# SPEC_A7_Power.net
KiCad netlist of a schematic drawn in Altium Designer
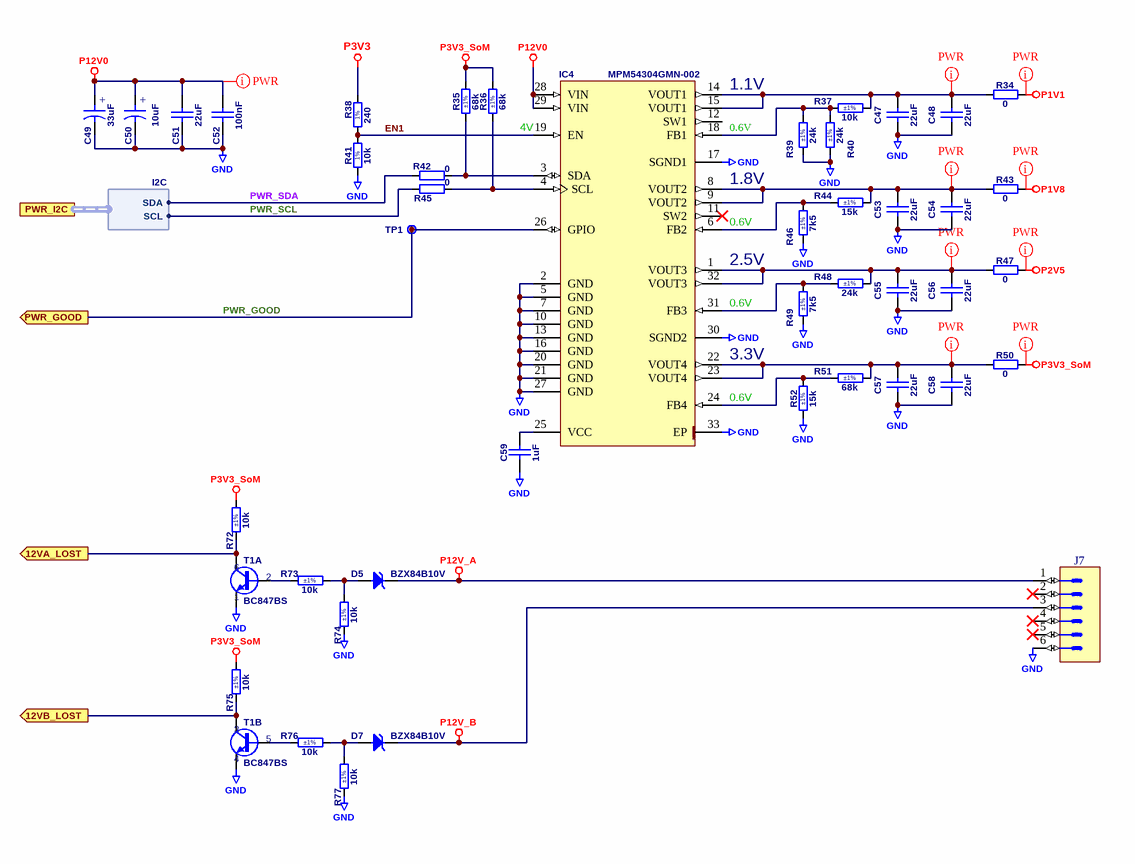
[diagram p0: SPEC_A7_Power.SchDoc]

(export (version "E")
  (design (tool "Eeschema 10.0.6"))
  (components
    (comp (ref "C47")
      (value "22uF")
      (footprint "CAPC2012X135N")
      (description "Non-polarised capacitor")
      (fields
        (field (name "MANUFACTURER PART NUMBER") "CC0805_22UF_16V_10%_X5R")
        (field (name "MANUFACTURER") "GENERIC")
        (field (name "AUTHOR") "CERN DEM JLC")
      )
      (libsource (lib "Capacitors") (part "Capacitor - non polarized"))
    )
    (comp (ref "C48")
      (value "22uF")
      (footprint "CAPC2012X135N")
      (description "Non-polarised capacitor")
      (fields
        (field (name "MANUFACTURER PART NUMBER") "CC0805_22UF_16V_10%_X5R")
        (field (name "MANUFACTURER") "GENERIC")
        (field (name "AUTHOR") "CERN DEM JLC")
      )
      (libsource (lib "Capacitors") (part "Capacitor - non polarized"))
    )
    (comp (ref "C49")
      (value "33uF")
      (footprint "CAPMP3528X210N")
      (description "Polarised capacitor")
      (fields
        (field (name "PART NUMBER") "CTE3528-21_33UF_16V_10%")
        (field (name "VOLTAGE") "16V")
        (field (name "AUTHOR") "CERN DEM JLC")
      )
      (libsource (lib "Capacitors") (part "Capacitor - polarized"))
    )
    (comp (ref "C50")
      (value "10uF")
      (footprint "CAPMP3216X180N")
      (description "Polarised capacitor")
      (fields
        (field (name "PART NUMBER") "CTE3216-18_10UF_16V_20%_AVX_TCJ")
        (field (name "VOLTAGE") "16V")
        (field (name "AUTHOR") "CERN DEM JLC")
      )
      (libsource (lib "Capacitors") (part "Capacitor - polarized"))
    )
    (comp (ref "C51")
      (value "22uF")
      (footprint "CAPC2012X135N")
      (description "Non-polarised capacitor")
      (fields
        (field (name "MANUFACTURER PART NUMBER") "CC0805_22UF_16V_10%_X5R")
        (field (name "MANUFACTURER") "GENERIC")
        (field (name "AUTHOR") "CERN DEM JLC")
      )
      (libsource (lib "Capacitors") (part "Capacitor - non polarized"))
    )
    (comp (ref "C52")
      (value "100nF")
      (footprint "CAPC1005X55N")
      (description "Non-polarised capacitor")
      (fields
        (field (name "PART NUMBER") "CC0402_100NF_16V_10%_X7R")
        (field (name "VOLTAGE") "16V")
        (field (name "AUTHOR") "CERN DEM JLC")
      )
      (libsource (lib "Capacitors") (part "Capacitor - non polarized"))
    )
    (comp (ref "C53")
      (value "22uF")
      (footprint "CAPC2012X135N")
      (description "Non-polarised capacitor")
      (fields
        (field (name "MANUFACTURER PART NUMBER") "CC0805_22UF_16V_10%_X5R")
        (field (name "MANUFACTURER") "GENERIC")
        (field (name "AUTHOR") "CERN DEM JLC")
      )
      (libsource (lib "Capacitors") (part "Capacitor - non polarized"))
    )
    (comp (ref "C54")
      (value "22uF")
      (footprint "CAPC2012X135N")
      (description "Non-polarised capacitor")
      (fields
        (field (name "MANUFACTURER PART NUMBER") "CC0805_22UF_16V_10%_X5R")
        (field (name "MANUFACTURER") "GENERIC")
        (field (name "AUTHOR") "CERN DEM JLC")
      )
      (libsource (lib "Capacitors") (part "Capacitor - non polarized"))
    )
    (comp (ref "C55")
      (value "22uF")
      (footprint "CAPC2012X135N")
      (description "Non-polarised capacitor")
      (fields
        (field (name "MANUFACTURER PART NUMBER") "CC0805_22UF_16V_10%_X5R")
        (field (name "MANUFACTURER") "GENERIC")
        (field (name "AUTHOR") "CERN DEM JLC")
      )
      (libsource (lib "Capacitors") (part "Capacitor - non polarized"))
    )
    (comp (ref "C56")
      (value "22uF")
      (footprint "CAPC2012X135N")
      (description "Non-polarised capacitor")
      (fields
        (field (name "MANUFACTURER PART NUMBER") "CC0805_22UF_16V_10%_X5R")
        (field (name "MANUFACTURER") "GENERIC")
        (field (name "AUTHOR") "CERN DEM JLC")
      )
      (libsource (lib "Capacitors") (part "Capacitor - non polarized"))
    )
    (comp (ref "C57")
      (value "22uF")
      (footprint "CAPC2012X135N")
      (description "Non-polarised capacitor")
      (fields
        (field (name "MANUFACTURER PART NUMBER") "CC0805_22UF_16V_10%_X5R")
        (field (name "MANUFACTURER") "GENERIC")
        (field (name "AUTHOR") "CERN DEM JLC")
      )
      (libsource (lib "Capacitors") (part "Capacitor - non polarized"))
    )
    (comp (ref "C58")
      (value "22uF")
      (footprint "CAPC2012X135N")
      (description "Non-polarised capacitor")
      (fields
        (field (name "MANUFACTURER PART NUMBER") "CC0805_22UF_16V_10%_X5R")
        (field (name "MANUFACTURER") "GENERIC")
        (field (name "AUTHOR") "CERN DEM JLC")
      )
      (libsource (lib "Capacitors") (part "Capacitor - non polarized"))
    )
    (comp (ref "C59")
      (value "1uF")
      (footprint "CAPC1005X55N")
      (description "Non-polarised capacitor")
      (fields
        (field (name "PART NUMBER") "CC0402_1UF_16V_10%_X5R")
        (field (name "VOLTAGE") "16V")
        (field (name "AUTHOR") "CERN DEM JLC")
      )
      (libsource (lib "Capacitors") (part "Capacitor - non polarized"))
    )
    (comp (ref "D5")
      (value "BZX84B10V")
      (footprint "SOT95P248X115-3N")
      (description "Diode Zener Anode Pin 1 Cathode Pin 3 (Pas de pin 2)")
      (fields
        (field (name "VOLTAGE") "10V")
        (field (name "POWER") "300mW")
        (field (name "AUTHOR") "CERN DEM JLC")
      )
      (libsource (lib "ICs And Semiconductors") (part "Diode Zener A1C3"))
    )
    (comp (ref "D7")
      (value "BZX84B10V")
      (footprint "SOT95P248X115-3N")
      (description "Diode Zener Anode Pin 1 Cathode Pin 3 (Pas de pin 2)")
      (fields
        (field (name "VOLTAGE") "10V")
        (field (name "POWER") "300mW")
        (field (name "AUTHOR") "CERN DEM JLC")
      )
      (libsource (lib "ICs And Semiconductors") (part "Diode Zener A1C3"))
    )
    (comp (ref "IC4")
      (value "MPM54304GMN-002")
      (footprint "MPS_MPM54304GMN")
      (description "Quad-Output Power Module with I2C and MTP")
      (fields
        (field (name "MANUFACTURER") "MPS (MONOLITIC  POWER SYSTEMS)")
        (field (name "AUTHOR") "CERN DEM BC")
      )
      (libsource (lib "ICs And Semiconductors") (part "MPM54304GMN"))
    )
    (comp (ref "J7")
      (value "Header 6")
      (footprint "3M_N2506-6002RB")
      (description "Connector 6 Male")
      (fields
        (field (name "PART NUMBER") "3M_N2506-6002RB")
        (field (name "MANUFACTURER") "3M")
        (field (name "AUTHOR") "CERN DEM JLC")
      )
      (libsource (lib "Connectors") (part "Connector 6 Male"))
    )
    (comp (ref "R34")
      (value "0")
      (footprint "RESC2012X60N")
      (description "Resistor")
      (fields
        (field (name "PART NUMBER") "R0805_0R_JUMPER")
        (field (name "MANUFACTURER") "GENERIC")
        (field (name "AUTHOR") "CERN DEM JLC")
      )
      (libsource (lib "Resistors") (part "Resistor"))
    )
    (comp (ref "R35")
      (value "68k")
      (footprint "RESC1005X40N")
      (description "Resistor - 1%")
      (fields
        (field (name "TOLERANCE") "±1%")
        (field (name "PART NUMBER") "R0402_68K_1%_0.0625W_100PPM")
        (field (name "POWER") "0.0625W")
        (field (name "AUTHOR") "CERN DEM JLC")
      )
      (libsource (lib "Resistors") (part "Resistor - 1%"))
    )
    (comp (ref "R36")
      (value "68k")
      (footprint "RESC1005X40N")
      (description "Resistor - 1%")
      (fields
        (field (name "TOLERANCE") "±1%")
        (field (name "PART NUMBER") "R0402_68K_1%_0.0625W_100PPM")
        (field (name "POWER") "0.0625W")
        (field (name "AUTHOR") "CERN DEM JLC")
      )
      (libsource (lib "Resistors") (part "Resistor - 1%"))
    )
    (comp (ref "R37")
      (value "10k")
      (footprint "RESC1005X40N")
      (description "Resistor - 1%")
      (fields
        (field (name "TOLERANCE") "±1%")
        (field (name "PART NUMBER") "R0402_10K_1%_0.0625W_100PPM")
        (field (name "POWER") "0.0625W")
        (field (name "AUTHOR") "CERN DEM JLC")
      )
      (libsource (lib "Resistors") (part "Resistor - 1%"))
    )
    (comp (ref "R38")
      (value "240")
      (footprint "RESC1005X40N")
      (description "Resistor - 1%")
      (fields
        (field (name "PART NUMBER") "R0402_240R_1%_0.0625W_100PPM")
        (field (name "POWER") "0.0625W")
        (field (name "AUTHOR") "CERN DEM JLC")
      )
      (libsource (lib "Resistors") (part "Resistor - 1%"))
    )
    (comp (ref "R39")
      (value "24k")
      (footprint "RESC1005X40N")
      (description "Resistor - 1%")
      (fields
        (field (name "TOLERANCE") "±1%")
        (field (name "PART NUMBER") "R0402_24K_1%_0.0625W_100PPM")
        (field (name "POWER") "0.0625W")
        (field (name "AUTHOR") "CERN DEM JLC")
      )
      (libsource (lib "Resistors") (part "Resistor - 1%"))
    )
    (comp (ref "R40")
      (value "24k")
      (footprint "RESC1005X40N")
      (description "Resistor - 1%")
      (fields
        (field (name "TOLERANCE") "±1%")
        (field (name "PART NUMBER") "R0402_24K_1%_0.0625W_100PPM")
        (field (name "POWER") "0.0625W")
        (field (name "AUTHOR") "CERN DEM JLC")
      )
      (libsource (lib "Resistors") (part "Resistor - 1%"))
    )
    (comp (ref "R41")
      (value "10k")
      (footprint "RESC1005X40N")
      (description "Resistor - 1%")
      (fields
        (field (name "PART NUMBER") "R0402_10K_1%_0.0625W_100PPM")
        (field (name "POWER") "0.0625W")
        (field (name "AUTHOR") "CERN DEM JLC")
      )
      (libsource (lib "Resistors") (part "Resistor - 1%"))
    )
    (comp (ref "R42")
      (value "0")
      (footprint "RESC1005X40N")
      (description "Resistor")
      (fields
        (field (name "PART NUMBER") "R0402_0R_JUMPER")
        (field (name "MANUFACTURER") "GENERIC")
        (field (name "AUTHOR") "CERN DEM JLC")
      )
      (libsource (lib "Resistors") (part "Resistor"))
    )
    (comp (ref "R43")
      (value "0")
      (footprint "RESC2012X60N")
      (description "Resistor")
      (fields
        (field (name "PART NUMBER") "R0805_0R_JUMPER")
        (field (name "MANUFACTURER") "GENERIC")
        (field (name "AUTHOR") "CERN DEM JLC")
      )
      (libsource (lib "Resistors") (part "Resistor"))
    )
    (comp (ref "R44")
      (value "15k")
      (footprint "RESC1005X40N")
      (description "Resistor - 1%")
      (fields
        (field (name "TOLERANCE") "±1%")
        (field (name "PART NUMBER") "R0402_15K_1%_0.0625W_100PPM")
        (field (name "POWER") "0.0625W")
        (field (name "AUTHOR") "CERN DEM JMW")
      )
      (libsource (lib "Resistors") (part "Resistor - 1%"))
    )
    (comp (ref "R45")
      (value "0")
      (footprint "RESC1005X40N")
      (description "Resistor")
      (fields
        (field (name "PART NUMBER") "R0402_0R_JUMPER")
        (field (name "MANUFACTURER") "GENERIC")
        (field (name "AUTHOR") "CERN DEM JLC")
      )
      (libsource (lib "Resistors") (part "Resistor"))
    )
    (comp (ref "R46")
      (value "7k5")
      (footprint "RESC1005X40N")
      (description "Resistor - 1%")
      (fields
        (field (name "TOLERANCE") "±1%")
        (field (name "PART NUMBER") "R0402_7K5_1%_0.0625W_100PPM")
        (field (name "POWER") "0.0625W")
        (field (name "AUTHOR") "CERN DEM JLC")
      )
      (libsource (lib "Resistors") (part "Resistor - 1%"))
    )
    (comp (ref "R47")
      (value "0")
      (footprint "RESC2012X60N")
      (description "Resistor")
      (fields
        (field (name "PART NUMBER") "R0805_0R_JUMPER")
        (field (name "MANUFACTURER") "GENERIC")
        (field (name "AUTHOR") "CERN DEM JLC")
      )
      (libsource (lib "Resistors") (part "Resistor"))
    )
    (comp (ref "R48")
      (value "24k")
      (footprint "RESC1005X40N")
      (description "Resistor - 1%")
      (fields
        (field (name "TOLERANCE") "±1%")
        (field (name "PART NUMBER") "R0402_24K_1%_0.0625W_100PPM")
        (field (name "POWER") "0.0625W")
        (field (name "AUTHOR") "CERN DEM JLC")
      )
      (libsource (lib "Resistors") (part "Resistor - 1%"))
    )
    (comp (ref "R49")
      (value "7k5")
      (footprint "RESC1005X40N")
      (description "Resistor - 1%")
      (fields
        (field (name "TOLERANCE") "±1%")
        (field (name "PART NUMBER") "R0402_7K5_1%_0.0625W_100PPM")
        (field (name "POWER") "0.0625W")
        (field (name "AUTHOR") "CERN DEM JLC")
      )
      (libsource (lib "Resistors") (part "Resistor - 1%"))
    )
    (comp (ref "R50")
      (value "0")
      (footprint "RESC2012X60N")
      (description "Resistor")
      (fields
        (field (name "PART NUMBER") "R0805_0R_JUMPER")
        (field (name "MANUFACTURER") "GENERIC")
        (field (name "AUTHOR") "CERN DEM JLC")
      )
      (libsource (lib "Resistors") (part "Resistor"))
    )
    (comp (ref "R51")
      (value "68k")
      (footprint "RESC1005X40N")
      (description "Resistor - 1%")
      (fields
        (field (name "TOLERANCE") "±1%")
        (field (name "PART NUMBER") "R0402_68K_1%_0.0625W_100PPM")
        (field (name "POWER") "0.0625W")
        (field (name "AUTHOR") "CERN DEM JLC")
      )
      (libsource (lib "Resistors") (part "Resistor - 1%"))
    )
    (comp (ref "R52")
      (value "15k")
      (footprint "RESC1005X40N")
      (description "Resistor - 1%")
      (fields
        (field (name "TOLERANCE") "±1%")
        (field (name "PART NUMBER") "R0402_15K_1%_0.0625W_100PPM")
        (field (name "POWER") "0.0625W")
        (field (name "AUTHOR") "CERN DEM JMW")
      )
      (libsource (lib "Resistors") (part "Resistor - 1%"))
    )
    (comp (ref "R72")
      (value "10k")
      (footprint "RESC1005X40N")
      (description "Resistor - 1%")
      (fields
        (field (name "TOLERANCE") "±1%")
        (field (name "PART NUMBER") "R0402_10K_1%_0.0625W_100PPM")
        (field (name "POWER") "0.0625W")
        (field (name "AUTHOR") "CERN DEM JLC")
      )
      (libsource (lib "Resistors") (part "Resistor - 1%"))
    )
    (comp (ref "R73")
      (value "10k")
      (footprint "RESC1005X40N")
      (description "Resistor - 1%")
      (fields
        (field (name "TOLERANCE") "±1%")
        (field (name "PART NUMBER") "R0402_10K_1%_0.0625W_100PPM")
        (field (name "POWER") "0.0625W")
        (field (name "AUTHOR") "CERN DEM JLC")
      )
      (libsource (lib "Resistors") (part "Resistor - 1%"))
    )
    (comp (ref "R74")
      (value "10k")
      (footprint "RESC1005X40N")
      (description "Resistor - 1%")
      (fields
        (field (name "TOLERANCE") "±1%")
        (field (name "PART NUMBER") "R0402_10K_1%_0.0625W_100PPM")
        (field (name "POWER") "0.0625W")
        (field (name "AUTHOR") "CERN DEM JLC")
      )
      (libsource (lib "Resistors") (part "Resistor - 1%"))
    )
    (comp (ref "R75")
      (value "10k")
      (footprint "RESC1005X40N")
      (description "Resistor - 1%")
      (fields
        (field (name "TOLERANCE") "±1%")
        (field (name "PART NUMBER") "R0402_10K_1%_0.0625W_100PPM")
        (field (name "POWER") "0.0625W")
        (field (name "AUTHOR") "CERN DEM JLC")
      )
      (libsource (lib "Resistors") (part "Resistor - 1%"))
    )
    (comp (ref "R76")
      (value "10k")
      (footprint "RESC1005X40N")
      (description "Resistor - 1%")
      (fields
        (field (name "TOLERANCE") "±1%")
        (field (name "PART NUMBER") "R0402_10K_1%_0.0625W_100PPM")
        (field (name "POWER") "0.0625W")
        (field (name "AUTHOR") "CERN DEM JLC")
      )
      (libsource (lib "Resistors") (part "Resistor - 1%"))
    )
    (comp (ref "R77")
      (value "10k")
      (footprint "RESC1005X40N")
      (description "Resistor - 1%")
      (fields
        (field (name "TOLERANCE") "±1%")
        (field (name "PART NUMBER") "R0402_10K_1%_0.0625W_100PPM")
        (field (name "POWER") "0.0625W")
        (field (name "AUTHOR") "CERN DEM JLC")
      )
      (libsource (lib "Resistors") (part "Resistor - 1%"))
    )
    (comp (ref "T1")
      (value "BC847BS")
      (footprint "SOT65P210X110-6N")
      (description "45V, 100mA Dual NPN General-Purpose Transistor")
      (fields (field (name "MANUFACTURER") "NXP SEMICONDUCTORS") (field (name "AUTHOR") "CERN DEM JMW"))
      (libsource (lib "ICs And Semiconductors") (part "BC847BS"))
    )
    (comp (ref "TP1")
      (value "Test Point")
      (footprint "TPS127")
      (fields (field (name "PART NUMBER") "SMD_PAD_1.27X1.27MM") (field (name "AUTHOR") "CERN DEM JLC"))
      (libsource (lib "Eletro-mechanical") (part "Test Point"))
    )
  )
  (nets
    (net (code "2") (name "/12VA_LOST") (class "Default")
      (node (ref "R72") (pin "1") (pinfunction "1_1") (pintype "passive"))
      (node (ref "T1") (pin "6") (pinfunction "C_6") (pintype "passive"))
    )
    (net (code "3") (name "/12VB_LOST") (class "Default")
      (node (ref "R75") (pin "1") (pinfunction "1_1") (pintype "passive"))
      (node (ref "T1") (pin "3") (pinfunction "C_3") (pintype "passive"))
    )
    (net (code "4") (name "/EN1") (class "Default")
      (node (ref "IC4") (pin "19") (pinfunction "EN_19") (pintype "input"))
      (node (ref "R38") (pin "1") (pinfunction "1_1") (pintype "passive"))
      (node (ref "R41") (pin "2") (pinfunction "2_2") (pintype "passive"))
    )
    (net (code "5") (name "/PWR_GOOD") (class "Default")
      (node (ref "IC4") (pin "26") (pinfunction "GPIO_26") (pintype "bidirectional"))
      (node (ref "TP1") (pin "1") (pinfunction "1_1") (pintype "bidirectional"))
    )
    (net (code "6") (name "/PWR_SCL") (class "Default")
      (node (ref "R45") (pin "1") (pinfunction "1_1") (pintype "passive"))
    )
    (net (code "7") (name "/PWR_SDA") (class "Default")
      (node (ref "R42") (pin "1") (pinfunction "1_1") (pintype "passive"))
    )
    (net (code "9") (name "GND") (class "Default")
      (node (ref "C47") (pin "1") (pinfunction "1_1") (pintype "passive"))
      (node (ref "C48") (pin "1") (pinfunction "1_1") (pintype "passive"))
      (node (ref "C49") (pin "2") (pinfunction "2_2") (pintype "passive"))
      (node (ref "C50") (pin "2") (pinfunction "2_2") (pintype "passive"))
      (node (ref "C51") (pin "1") (pinfunction "1_1") (pintype "passive"))
      (node (ref "C52") (pin "1") (pinfunction "1_1") (pintype "passive"))
      (node (ref "C53") (pin "1") (pinfunction "1_1") (pintype "passive"))
      (node (ref "C54") (pin "1") (pinfunction "1_1") (pintype "passive"))
      (node (ref "C55") (pin "1") (pinfunction "1_1") (pintype "passive"))
      (node (ref "C56") (pin "1") (pinfunction "1_1") (pintype "passive"))
      (node (ref "C57") (pin "1") (pinfunction "1_1") (pintype "passive"))
      (node (ref "C58") (pin "1") (pinfunction "1_1") (pintype "passive"))
      (node (ref "C59") (pin "1") (pinfunction "1_1") (pintype "passive"))
      (node (ref "IC4") (pin "10") (pinfunction "GND_10") (pintype "power_in"))
      (node (ref "IC4") (pin "13") (pinfunction "GND_13") (pintype "power_in"))
      (node (ref "IC4") (pin "16") (pinfunction "GND_16") (pintype "power_in"))
      (node (ref "IC4") (pin "17") (pinfunction "SGND1_17") (pintype "power_in"))
      (node (ref "IC4") (pin "2") (pinfunction "GND_2") (pintype "power_in"))
      (node (ref "IC4") (pin "20") (pinfunction "GND_20") (pintype "power_in"))
      (node (ref "IC4") (pin "21") (pinfunction "GND_21") (pintype "power_in"))
      (node (ref "IC4") (pin "27") (pinfunction "GND_27") (pintype "power_in"))
      (node (ref "IC4") (pin "30") (pinfunction "SGND2_30") (pintype "power_in"))
      (node (ref "IC4") (pin "33") (pinfunction "EP_33") (pintype "power_in"))
      (node (ref "IC4") (pin "5") (pinfunction "GND_5") (pintype "power_in"))
      (node (ref "IC4") (pin "7") (pinfunction "GND_7") (pintype "power_in"))
      (node (ref "J7") (pin "6") (pinfunction "6_6") (pintype "bidirectional"))
      (node (ref "R39") (pin "1") (pinfunction "1_1") (pintype "passive"))
      (node (ref "R40") (pin "1") (pinfunction "1_1") (pintype "passive"))
      (node (ref "R41") (pin "1") (pinfunction "1_1") (pintype "passive"))
      (node (ref "R46") (pin "1") (pinfunction "1_1") (pintype "passive"))
      (node (ref "R49") (pin "1") (pinfunction "1_1") (pintype "passive"))
      (node (ref "R52") (pin "1") (pinfunction "1_1") (pintype "passive"))
      (node (ref "R74") (pin "1") (pinfunction "1_1") (pintype "passive"))
      (node (ref "R77") (pin "1") (pinfunction "1_1") (pintype "passive"))
      (node (ref "T1") (pin "1") (pinfunction "E_1") (pintype "passive"))
      (node (ref "T1") (pin "4") (pinfunction "E_4") (pintype "passive"))
    )
    (net (code "10") (name "Net-(C47-Pad2)") (class "Default")
      (node (ref "C47") (pin "2") (pinfunction "2_2") (pintype "passive"))
      (node (ref "C48") (pin "2") (pinfunction "2_2") (pintype "passive"))
      (node (ref "IC4") (pin "14") (pinfunction "VOUT1_14") (pintype "output"))
      (node (ref "IC4") (pin "15") (pinfunction "VOUT1_15") (pintype "output"))
      (node (ref "R34") (pin "1") (pinfunction "1_1") (pintype "passive"))
      (node (ref "R37") (pin "2") (pinfunction "2_2") (pintype "passive"))
    )
    (net (code "11") (name "Net-(C53-Pad2)") (class "Default")
      (node (ref "C53") (pin "2") (pinfunction "2_2") (pintype "passive"))
      (node (ref "C54") (pin "2") (pinfunction "2_2") (pintype "passive"))
      (node (ref "IC4") (pin "8") (pinfunction "VOUT2_8") (pintype "output"))
      (node (ref "IC4") (pin "9") (pinfunction "VOUT2_9") (pintype "output"))
      (node (ref "R43") (pin "1") (pinfunction "1_1") (pintype "passive"))
      (node (ref "R44") (pin "2") (pinfunction "2_2") (pintype "passive"))
    )
    (net (code "12") (name "Net-(C55-Pad2)") (class "Default")
      (node (ref "C55") (pin "2") (pinfunction "2_2") (pintype "passive"))
      (node (ref "C56") (pin "2") (pinfunction "2_2") (pintype "passive"))
      (node (ref "IC4") (pin "1") (pinfunction "VOUT3_1") (pintype "output"))
      (node (ref "IC4") (pin "32") (pinfunction "VOUT3_32") (pintype "output"))
      (node (ref "R47") (pin "1") (pinfunction "1_1") (pintype "passive"))
      (node (ref "R48") (pin "2") (pinfunction "2_2") (pintype "passive"))
    )
    (net (code "13") (name "Net-(C57-Pad2)") (class "Default")
      (node (ref "C57") (pin "2") (pinfunction "2_2") (pintype "passive"))
      (node (ref "C58") (pin "2") (pinfunction "2_2") (pintype "passive"))
      (node (ref "IC4") (pin "22") (pinfunction "VOUT4_22") (pintype "output"))
      (node (ref "IC4") (pin "23") (pinfunction "VOUT4_23") (pintype "output"))
      (node (ref "R50") (pin "1") (pinfunction "1_1") (pintype "passive"))
      (node (ref "R51") (pin "2") (pinfunction "2_2") (pintype "passive"))
    )
    (net (code "14") (name "Net-(D5-A)") (class "Default")
      (node (ref "D5") (pin "1") (pinfunction "A_1") (pintype "passive"))
      (node (ref "R73") (pin "2") (pinfunction "2_2") (pintype "passive"))
      (node (ref "R74") (pin "2") (pinfunction "2_2") (pintype "passive"))
    )
    (net (code "15") (name "Net-(D7-A)") (class "Default")
      (node (ref "D7") (pin "1") (pinfunction "A_1") (pintype "passive"))
      (node (ref "R76") (pin "2") (pinfunction "2_2") (pintype "passive"))
      (node (ref "R77") (pin "2") (pinfunction "2_2") (pintype "passive"))
    )
    (net (code "16") (name "Net-(IC4-FB1)") (class "Default")
      (node (ref "IC4") (pin "18") (pinfunction "FB1_18") (pintype "input"))
      (node (ref "R37") (pin "1") (pinfunction "1_1") (pintype "passive"))
      (node (ref "R39") (pin "2") (pinfunction "2_2") (pintype "passive"))
      (node (ref "R40") (pin "2") (pinfunction "2_2") (pintype "passive"))
    )
    (net (code "17") (name "Net-(IC4-FB2)") (class "Default")
      (node (ref "IC4") (pin "6") (pinfunction "FB2_6") (pintype "input"))
      (node (ref "R44") (pin "1") (pinfunction "1_1") (pintype "passive"))
      (node (ref "R46") (pin "2") (pinfunction "2_2") (pintype "passive"))
    )
    (net (code "18") (name "Net-(IC4-FB3)") (class "Default")
      (node (ref "IC4") (pin "31") (pinfunction "FB3_31") (pintype "input"))
      (node (ref "R48") (pin "1") (pinfunction "1_1") (pintype "passive"))
      (node (ref "R49") (pin "2") (pinfunction "2_2") (pintype "passive"))
    )
    (net (code "19") (name "Net-(IC4-FB4)") (class "Default")
      (node (ref "IC4") (pin "24") (pinfunction "FB4_24") (pintype "input"))
      (node (ref "R51") (pin "1") (pinfunction "1_1") (pintype "passive"))
      (node (ref "R52") (pin "2") (pinfunction "2_2") (pintype "passive"))
    )
    (net (code "20") (name "Net-(IC4-SCL)") (class "Default")
      (node (ref "IC4") (pin "4") (pinfunction "SCL_4") (pintype "input"))
      (node (ref "R36") (pin "1") (pinfunction "1_1") (pintype "passive"))
      (node (ref "R45") (pin "2") (pinfunction "2_2") (pintype "passive"))
    )
    (net (code "21") (name "Net-(IC4-SDA)") (class "Default")
      (node (ref "IC4") (pin "3") (pinfunction "SDA_3") (pintype "bidirectional"))
      (node (ref "R35") (pin "1") (pinfunction "1_1") (pintype "passive"))
      (node (ref "R42") (pin "2") (pinfunction "2_2") (pintype "passive"))
    )
    (net (code "22") (name "Net-(IC4-VCC)") (class "Default")
      (node (ref "C59") (pin "2") (pinfunction "2_2") (pintype "passive"))
      (node (ref "IC4") (pin "25") (pinfunction "VCC_25") (pintype "power_in"))
    )
    (net (code "23") (name "Net-(T1A-B)") (class "Default")
      (node (ref "R73") (pin "1") (pinfunction "1_1") (pintype "passive"))
      (node (ref "T1") (pin "2") (pinfunction "B_2") (pintype "passive"))
    )
    (net (code "24") (name "Net-(T1B-B)") (class "Default")
      (node (ref "R76") (pin "1") (pinfunction "1_1") (pintype "passive"))
      (node (ref "T1") (pin "5") (pinfunction "B_5") (pintype "passive"))
    )
    (net (code "25") (name "P1V1") (class "Default")
      (node (ref "R34") (pin "2") (pinfunction "2_2") (pintype "passive"))
    )
    (net (code "26") (name "P1V8") (class "Default")
      (node (ref "R43") (pin "2") (pinfunction "2_2") (pintype "passive"))
    )
    (net (code "27") (name "P2V5") (class "Default")
      (node (ref "R47") (pin "2") (pinfunction "2_2") (pintype "passive"))
    )
    (net (code "28") (name "P3V3") (class "Default")
      (node (ref "R38") (pin "2") (pinfunction "2_2") (pintype "passive"))
    )
    (net (code "29") (name "P3V3_SoM") (class "Default")
      (node (ref "R35") (pin "2") (pinfunction "2_2") (pintype "passive"))
      (node (ref "R36") (pin "2") (pinfunction "2_2") (pintype "passive"))
      (node (ref "R50") (pin "2") (pinfunction "2_2") (pintype "passive"))
      (node (ref "R72") (pin "2") (pinfunction "2_2") (pintype "passive"))
      (node (ref "R75") (pin "2") (pinfunction "2_2") (pintype "passive"))
    )
    (net (code "30") (name "P12V0") (class "Default")
      (node (ref "C49") (pin "1") (pinfunction "1_1") (pintype "passive"))
      (node (ref "C50") (pin "1") (pinfunction "1_1") (pintype "passive"))
      (node (ref "C51") (pin "2") (pinfunction "2_2") (pintype "passive"))
      (node (ref "C52") (pin "2") (pinfunction "2_2") (pintype "passive"))
      (node (ref "IC4") (pin "28") (pinfunction "VIN_28") (pintype "input"))
      (node (ref "IC4") (pin "29") (pinfunction "VIN_29") (pintype "input"))
    )
    (net (code "31") (name "P12V_A") (class "Default")
      (node (ref "D5") (pin "3") (pinfunction "C_3") (pintype "passive"))
      (node (ref "J7") (pin "1") (pinfunction "1_1") (pintype "bidirectional"))
    )
    (net (code "32") (name "P12V_B") (class "Default")
      (node (ref "D7") (pin "3") (pinfunction "C_3") (pintype "passive"))
      (node (ref "J7") (pin "3") (pinfunction "3_3") (pintype "bidirectional"))
    )
    (net (code "33") (name "unconnected-(IC4-SW1-Pad12)") (class "Default")
      (node (ref "IC4") (pin "12") (pinfunction "SW1_12") (pintype "output"))
    )
    (net (code "34") (name "unconnected-(IC4-SW2-Pad11)") (class "Default")
      (node (ref "IC4") (pin "11") (pinfunction "SW2_11") (pintype "output+no_connect"))
    )
    (net (code "35") (name "unconnected-(J7-Pad2)") (class "Default")
      (node (ref "J7") (pin "2") (pinfunction "2_2") (pintype "bidirectional+no_connect"))
    )
    (net (code "36") (name "unconnected-(J7-Pad4)") (class "Default")
      (node (ref "J7") (pin "4") (pinfunction "4_4") (pintype "bidirectional+no_connect"))
    )
    (net (code "37") (name "unconnected-(J7-Pad5)") (class "Default")
      (node (ref "J7") (pin "5") (pinfunction "5_5") (pintype "bidirectional+no_connect"))
    )
  )
)
